# SCH.net
KiCad netlist of a schematic drawn in Altium Designer
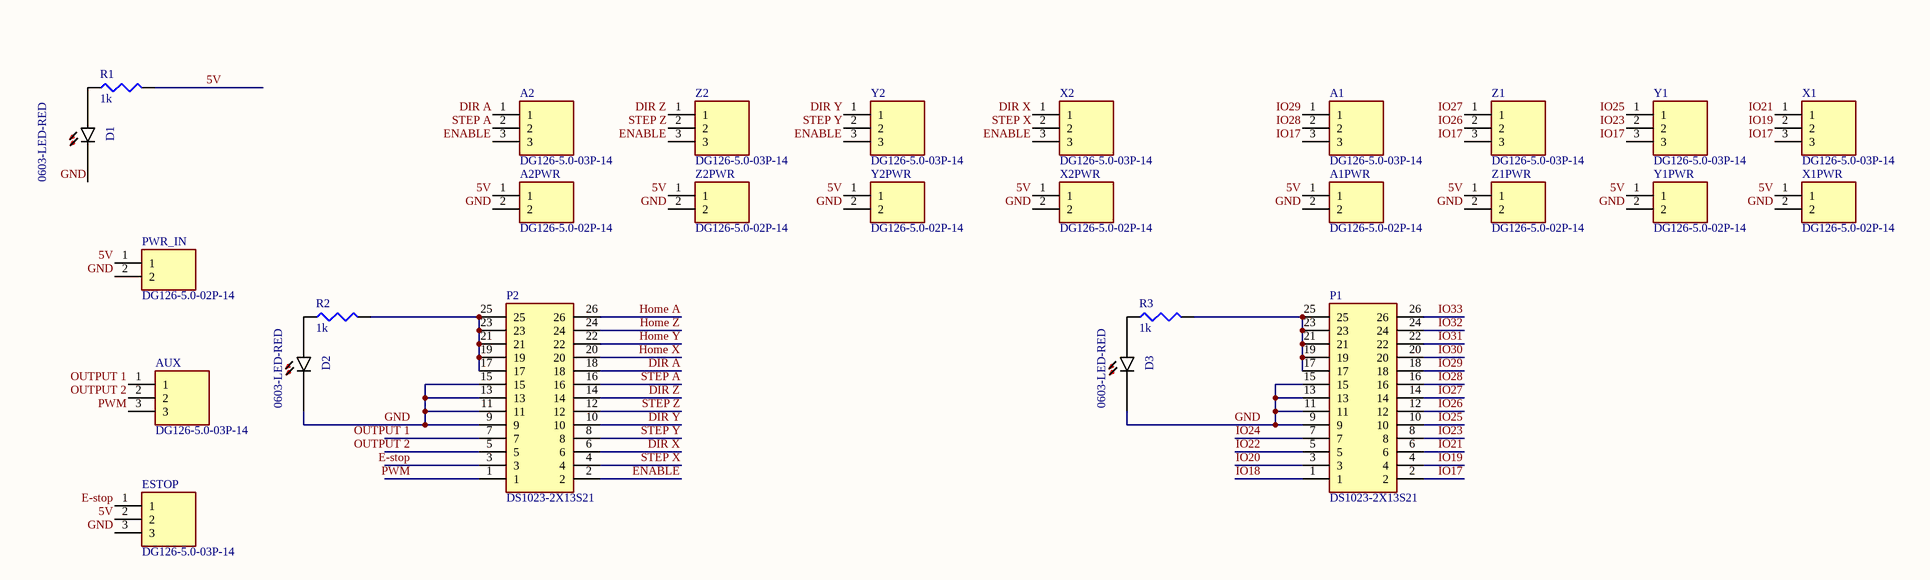
[diagram p0: SCH.SchDoc]

(export (version "E")
  (design (tool "Eeschema 10.0.6"))
  (components
    (comp (ref "A1")
      (value "DG126-5.0-03P-14")
      (footprint "SamacSys:DG1265003P1400AH")
      (description "Connector")
      (libsource (lib "*") (part "DG126-5.0-03P-14-00AH"))
    )
    (comp (ref "A1PWR")
      (value "DG126-5.0-02P-14")
      (footprint "SamacSys:DG1265002P1400AH")
      (description "Connector")
      (libsource (lib "*") (part "DG126-5.0-02P-14-00AH"))
    )
    (comp (ref "A2")
      (value "DG126-5.0-03P-14")
      (footprint "SamacSys:DG1265003P1400AH")
      (description "Connector")
      (libsource (lib "*") (part "DG126-5.0-03P-14-00AH"))
    )
    (comp (ref "A2PWR")
      (value "DG126-5.0-02P-14")
      (footprint "SamacSys:DG1265002P1400AH")
      (description "Connector")
      (libsource (lib "*") (part "DG126-5.0-02P-14-00AH"))
    )
    (comp (ref "AUX")
      (value "DG126-5.0-03P-14")
      (footprint "SamacSys:DG1265003P1400AH")
      (description "Connector")
      (libsource (lib "*") (part "DG126-5.0-03P-14-00AH"))
    )
    (comp (ref "D1")
      (value "0603-LED-RED")
      (footprint "*LEDM1608X80_LTE-C1906R-14(Primary)")
      (description "Red 620nm LED Indication - Discrete 2.2V 0603 (1608 Metric)")
      (fields (field (name "MP") "LTST-C194KRKT or SML-D12U1WT86"))
      (libsource (lib "lib") (part "0603-LED-RED"))
    )
    (comp (ref "D2")
      (value "0603-LED-RED")
      (footprint "*LEDM1608X80_LTE-C1906R-14(Primary)")
      (description "Red 620nm LED Indication - Discrete 2.2V 0603 (1608 Metric)")
      (fields (field (name "MP") "LTST-C194KRKT or SML-D12U1WT86"))
      (libsource (lib "lib") (part "0603-LED-RED"))
    )
    (comp (ref "D3")
      (value "0603-LED-RED")
      (footprint "*LEDM1608X80_LTE-C1906R-14(Primary)")
      (description "Red 620nm LED Indication - Discrete 2.2V 0603 (1608 Metric)")
      (fields (field (name "MP") "LTST-C194KRKT or SML-D12U1WT86"))
      (libsource (lib "lib") (part "0603-LED-RED"))
    )
    (comp (ref "ESTOP")
      (value "DG126-5.0-03P-14")
      (footprint "SamacSys:DG1265003P1400AH")
      (description "Connector")
      (libsource (lib "*") (part "DG126-5.0-03P-14-00AH"))
    )
    (comp (ref "P1")
      (value "DS1023-2X13S21")
      (footprint "SamacSys:DS10232X13S21")
      (description "Connector")
      (libsource (lib "*") (part "DS1023-2X13S21"))
    )
    (comp (ref "P2")
      (value "DS1023-2X13S21")
      (footprint "SamacSys:DS10232X13S21")
      (description "Connector")
      (libsource (lib "*") (part "DS1023-2X13S21"))
    )
    (comp (ref "PWR_IN")
      (value "DG126-5.0-02P-14")
      (footprint "SamacSys:DG1265002P1400AH")
      (description "Connector")
      (libsource (lib "*") (part "DG126-5.0-02P-14-00AH"))
    )
    (comp (ref "R1")
      (value "1k")
      (footprint "J1-0603")
      (description "1 kOhms ±1% 0.1W, 1/10W Chip Resistor 0603 (1608 Metric) Moisture Resistant Thick Film")
      (fields (field (name "MF") "Yageo or NXP") (field (name "MP") "RC0603FR-071KL"))
      (libsource (lib "lib") (part "RC0603FR-071KL"))
    )
    (comp (ref "R2")
      (value "1k")
      (footprint "J1-0603")
      (description "1 kOhms ±1% 0.1W, 1/10W Chip Resistor 0603 (1608 Metric) Moisture Resistant Thick Film")
      (fields (field (name "MF") "Yageo or NXP") (field (name "MP") "RC0603FR-071KL"))
      (libsource (lib "lib") (part "RC0603FR-071KL"))
    )
    (comp (ref "R3")
      (value "1k")
      (footprint "J1-0603")
      (description "1 kOhms ±1% 0.1W, 1/10W Chip Resistor 0603 (1608 Metric) Moisture Resistant Thick Film")
      (fields (field (name "MF") "Yageo or NXP") (field (name "MP") "RC0603FR-071KL"))
      (libsource (lib "lib") (part "RC0603FR-071KL"))
    )
    (comp (ref "X1")
      (value "DG126-5.0-03P-14")
      (footprint "SamacSys:DG1265003P1400AH")
      (description "Connector")
      (libsource (lib "*") (part "DG126-5.0-03P-14-00AH"))
    )
    (comp (ref "X1PWR")
      (value "DG126-5.0-02P-14")
      (footprint "SamacSys:DG1265002P1400AH")
      (description "Connector")
      (libsource (lib "*") (part "DG126-5.0-02P-14-00AH"))
    )
    (comp (ref "X2")
      (value "DG126-5.0-03P-14")
      (footprint "SamacSys:DG1265003P1400AH")
      (description "Connector")
      (libsource (lib "*") (part "DG126-5.0-03P-14-00AH"))
    )
    (comp (ref "X2PWR")
      (value "DG126-5.0-02P-14")
      (footprint "SamacSys:DG1265002P1400AH")
      (description "Connector")
      (libsource (lib "*") (part "DG126-5.0-02P-14-00AH"))
    )
    (comp (ref "Y1")
      (value "DG126-5.0-03P-14")
      (footprint "SamacSys:DG1265003P1400AH")
      (description "Connector")
      (libsource (lib "*") (part "DG126-5.0-03P-14-00AH"))
    )
    (comp (ref "Y1PWR")
      (value "DG126-5.0-02P-14")
      (footprint "SamacSys:DG1265002P1400AH")
      (description "Connector")
      (libsource (lib "*") (part "DG126-5.0-02P-14-00AH"))
    )
    (comp (ref "Y2")
      (value "DG126-5.0-03P-14")
      (footprint "SamacSys:DG1265003P1400AH")
      (description "Connector")
      (libsource (lib "*") (part "DG126-5.0-03P-14-00AH"))
    )
    (comp (ref "Y2PWR")
      (value "DG126-5.0-02P-14")
      (footprint "SamacSys:DG1265002P1400AH")
      (description "Connector")
      (libsource (lib "*") (part "DG126-5.0-02P-14-00AH"))
    )
    (comp (ref "Z1")
      (value "DG126-5.0-03P-14")
      (footprint "SamacSys:DG1265003P1400AH")
      (description "Connector")
      (libsource (lib "*") (part "DG126-5.0-03P-14-00AH"))
    )
    (comp (ref "Z1PWR")
      (value "DG126-5.0-02P-14")
      (footprint "SamacSys:DG1265002P1400AH")
      (description "Connector")
      (libsource (lib "*") (part "DG126-5.0-02P-14-00AH"))
    )
    (comp (ref "Z2")
      (value "DG126-5.0-03P-14")
      (footprint "SamacSys:DG1265003P1400AH")
      (description "Connector")
      (libsource (lib "*") (part "DG126-5.0-03P-14-00AH"))
    )
    (comp (ref "Z2PWR")
      (value "DG126-5.0-02P-14")
      (footprint "SamacSys:DG1265002P1400AH")
      (description "Connector")
      (libsource (lib "*") (part "DG126-5.0-02P-14-00AH"))
    )
  )
  (nets
    (net (code "1") (name "/5V") (class "Default")
      (node (ref "A1PWR") (pin "1") (pinfunction "1_1") (pintype "passive"))
      (node (ref "A2PWR") (pin "1") (pinfunction "1_1") (pintype "passive"))
      (node (ref "ESTOP") (pin "2") (pinfunction "2_2") (pintype "passive"))
      (node (ref "PWR_IN") (pin "1") (pinfunction "1_1") (pintype "passive"))
      (node (ref "R1") (pin "2") (pinfunction "2_2") (pintype "passive"))
      (node (ref "X1PWR") (pin "1") (pinfunction "1_1") (pintype "passive"))
      (node (ref "X2PWR") (pin "1") (pinfunction "1_1") (pintype "passive"))
      (node (ref "Y1PWR") (pin "1") (pinfunction "1_1") (pintype "passive"))
      (node (ref "Y2PWR") (pin "1") (pinfunction "1_1") (pintype "passive"))
      (node (ref "Z1PWR") (pin "1") (pinfunction "1_1") (pintype "passive"))
      (node (ref "Z2PWR") (pin "1") (pinfunction "1_1") (pintype "passive"))
    )
    (net (code "2") (name "/DIR A") (class "Default")
      (node (ref "A2") (pin "1") (pinfunction "1_1") (pintype "passive"))
      (node (ref "P2") (pin "18") (pinfunction "18_18") (pintype "passive"))
    )
    (net (code "3") (name "/DIR X") (class "Default")
      (node (ref "P2") (pin "6") (pinfunction "6_6") (pintype "passive"))
      (node (ref "X2") (pin "1") (pinfunction "1_1") (pintype "passive"))
    )
    (net (code "4") (name "/DIR Y") (class "Default")
      (node (ref "P2") (pin "10") (pinfunction "10_10") (pintype "passive"))
      (node (ref "Y2") (pin "1") (pinfunction "1_1") (pintype "passive"))
    )
    (net (code "5") (name "/DIR Z") (class "Default")
      (node (ref "P2") (pin "14") (pinfunction "14_14") (pintype "passive"))
      (node (ref "Z2") (pin "1") (pinfunction "1_1") (pintype "passive"))
    )
    (net (code "6") (name "/E-stop") (class "Default")
      (node (ref "ESTOP") (pin "1") (pinfunction "1_1") (pintype "passive"))
      (node (ref "P2") (pin "3") (pinfunction "3_3") (pintype "passive"))
    )
    (net (code "7") (name "/ENABLE") (class "Default")
      (node (ref "A2") (pin "3") (pinfunction "3_3") (pintype "passive"))
      (node (ref "P2") (pin "2") (pinfunction "2_2") (pintype "passive"))
      (node (ref "X2") (pin "3") (pinfunction "3_3") (pintype "passive"))
      (node (ref "Y2") (pin "3") (pinfunction "3_3") (pintype "passive"))
      (node (ref "Z2") (pin "3") (pinfunction "3_3") (pintype "passive"))
    )
    (net (code "8") (name "/GND") (class "Default")
      (node (ref "A1PWR") (pin "2") (pinfunction "2_2") (pintype "passive"))
      (node (ref "A2PWR") (pin "2") (pinfunction "2_2") (pintype "passive"))
      (node (ref "D1") (pin "C") (pinfunction "C_C") (pintype "passive"))
      (node (ref "D2") (pin "C") (pinfunction "C_C") (pintype "passive"))
      (node (ref "D3") (pin "C") (pinfunction "C_C") (pintype "passive"))
      (node (ref "ESTOP") (pin "3") (pinfunction "3_3") (pintype "passive"))
      (node (ref "P1") (pin "11") (pinfunction "11_11") (pintype "passive"))
      (node (ref "P1") (pin "13") (pinfunction "13_13") (pintype "passive"))
      (node (ref "P1") (pin "15") (pinfunction "15_15") (pintype "passive"))
      (node (ref "P1") (pin "9") (pinfunction "9_9") (pintype "passive"))
      (node (ref "P2") (pin "11") (pinfunction "11_11") (pintype "passive"))
      (node (ref "P2") (pin "13") (pinfunction "13_13") (pintype "passive"))
      (node (ref "P2") (pin "15") (pinfunction "15_15") (pintype "passive"))
      (node (ref "P2") (pin "9") (pinfunction "9_9") (pintype "passive"))
      (node (ref "PWR_IN") (pin "2") (pinfunction "2_2") (pintype "passive"))
      (node (ref "X1PWR") (pin "2") (pinfunction "2_2") (pintype "passive"))
      (node (ref "X2PWR") (pin "2") (pinfunction "2_2") (pintype "passive"))
      (node (ref "Y1PWR") (pin "2") (pinfunction "2_2") (pintype "passive"))
      (node (ref "Y2PWR") (pin "2") (pinfunction "2_2") (pintype "passive"))
      (node (ref "Z1PWR") (pin "2") (pinfunction "2_2") (pintype "passive"))
      (node (ref "Z2PWR") (pin "2") (pinfunction "2_2") (pintype "passive"))
    )
    (net (code "9") (name "/Home A") (class "Default")
      (node (ref "P2") (pin "26") (pinfunction "26_26") (pintype "passive"))
    )
    (net (code "10") (name "/Home X") (class "Default")
      (node (ref "P2") (pin "20") (pinfunction "20_20") (pintype "passive"))
    )
    (net (code "11") (name "/Home Y") (class "Default")
      (node (ref "P2") (pin "22") (pinfunction "22_22") (pintype "passive"))
    )
    (net (code "12") (name "/Home Z") (class "Default")
      (node (ref "P2") (pin "24") (pinfunction "24_24") (pintype "passive"))
    )
    (net (code "13") (name "/IO17") (class "Default")
      (node (ref "A1") (pin "3") (pinfunction "3_3") (pintype "passive"))
      (node (ref "P1") (pin "2") (pinfunction "2_2") (pintype "passive"))
      (node (ref "X1") (pin "3") (pinfunction "3_3") (pintype "passive"))
      (node (ref "Y1") (pin "3") (pinfunction "3_3") (pintype "passive"))
      (node (ref "Z1") (pin "3") (pinfunction "3_3") (pintype "passive"))
    )
    (net (code "14") (name "/IO18") (class "Default")
      (node (ref "P1") (pin "1") (pinfunction "1_1") (pintype "passive"))
    )
    (net (code "15") (name "/IO19") (class "Default")
      (node (ref "P1") (pin "4") (pinfunction "4_4") (pintype "passive"))
      (node (ref "X1") (pin "2") (pinfunction "2_2") (pintype "passive"))
    )
    (net (code "16") (name "/IO20") (class "Default")
      (node (ref "P1") (pin "3") (pinfunction "3_3") (pintype "passive"))
    )
    (net (code "17") (name "/IO21") (class "Default")
      (node (ref "P1") (pin "6") (pinfunction "6_6") (pintype "passive"))
      (node (ref "X1") (pin "1") (pinfunction "1_1") (pintype "passive"))
    )
    (net (code "18") (name "/IO22") (class "Default")
      (node (ref "P1") (pin "5") (pinfunction "5_5") (pintype "passive"))
    )
    (net (code "19") (name "/IO23") (class "Default")
      (node (ref "P1") (pin "8") (pinfunction "8_8") (pintype "passive"))
      (node (ref "Y1") (pin "2") (pinfunction "2_2") (pintype "passive"))
    )
    (net (code "20") (name "/IO24") (class "Default")
      (node (ref "P1") (pin "7") (pinfunction "7_7") (pintype "passive"))
    )
    (net (code "21") (name "/IO25") (class "Default")
      (node (ref "P1") (pin "10") (pinfunction "10_10") (pintype "passive"))
      (node (ref "Y1") (pin "1") (pinfunction "1_1") (pintype "passive"))
    )
    (net (code "22") (name "/IO26") (class "Default")
      (node (ref "P1") (pin "12") (pinfunction "12_12") (pintype "passive"))
      (node (ref "Z1") (pin "2") (pinfunction "2_2") (pintype "passive"))
    )
    (net (code "23") (name "/IO27") (class "Default")
      (node (ref "P1") (pin "14") (pinfunction "14_14") (pintype "passive"))
      (node (ref "Z1") (pin "1") (pinfunction "1_1") (pintype "passive"))
    )
    (net (code "24") (name "/IO28") (class "Default")
      (node (ref "A1") (pin "2") (pinfunction "2_2") (pintype "passive"))
      (node (ref "P1") (pin "16") (pinfunction "16_16") (pintype "passive"))
    )
    (net (code "25") (name "/IO29") (class "Default")
      (node (ref "A1") (pin "1") (pinfunction "1_1") (pintype "passive"))
      (node (ref "P1") (pin "18") (pinfunction "18_18") (pintype "passive"))
    )
    (net (code "26") (name "/IO30") (class "Default")
      (node (ref "P1") (pin "20") (pinfunction "20_20") (pintype "passive"))
    )
    (net (code "27") (name "/IO31") (class "Default")
      (node (ref "P1") (pin "22") (pinfunction "22_22") (pintype "passive"))
    )
    (net (code "28") (name "/IO32") (class "Default")
      (node (ref "P1") (pin "24") (pinfunction "24_24") (pintype "passive"))
    )
    (net (code "29") (name "/IO33") (class "Default")
      (node (ref "P1") (pin "26") (pinfunction "26_26") (pintype "passive"))
    )
    (net (code "30") (name "/OUTPUT 1") (class "Default")
      (node (ref "AUX") (pin "1") (pinfunction "1_1") (pintype "passive"))
      (node (ref "P2") (pin "7") (pinfunction "7_7") (pintype "passive"))
    )
    (net (code "31") (name "/OUTPUT 2") (class "Default")
      (node (ref "AUX") (pin "2") (pinfunction "2_2") (pintype "passive"))
      (node (ref "P2") (pin "5") (pinfunction "5_5") (pintype "passive"))
    )
    (net (code "32") (name "/PWM") (class "Default")
      (node (ref "AUX") (pin "3") (pinfunction "3_3") (pintype "passive"))
      (node (ref "P2") (pin "1") (pinfunction "1_1") (pintype "passive"))
    )
    (net (code "33") (name "/STEP A") (class "Default")
      (node (ref "A2") (pin "2") (pinfunction "2_2") (pintype "passive"))
      (node (ref "P2") (pin "16") (pinfunction "16_16") (pintype "passive"))
    )
    (net (code "34") (name "/STEP X") (class "Default")
      (node (ref "P2") (pin "4") (pinfunction "4_4") (pintype "passive"))
      (node (ref "X2") (pin "2") (pinfunction "2_2") (pintype "passive"))
    )
    (net (code "35") (name "/STEP Y") (class "Default")
      (node (ref "P2") (pin "8") (pinfunction "8_8") (pintype "passive"))
      (node (ref "Y2") (pin "2") (pinfunction "2_2") (pintype "passive"))
    )
    (net (code "36") (name "/STEP Z") (class "Default")
      (node (ref "P2") (pin "12") (pinfunction "12_12") (pintype "passive"))
      (node (ref "Z2") (pin "2") (pinfunction "2_2") (pintype "passive"))
    )
    (net (code "37") (name "Net-(D1-PadA)") (class "Default")
      (node (ref "D1") (pin "A") (pinfunction "A_A") (pintype "passive"))
      (node (ref "R1") (pin "1") (pinfunction "1_1") (pintype "passive"))
    )
    (net (code "38") (name "Net-(D2-PadA)") (class "Default")
      (node (ref "D2") (pin "A") (pinfunction "A_A") (pintype "passive"))
      (node (ref "R2") (pin "1") (pinfunction "1_1") (pintype "passive"))
    )
    (net (code "39") (name "Net-(D3-PadA)") (class "Default")
      (node (ref "D3") (pin "A") (pinfunction "A_A") (pintype "passive"))
      (node (ref "R3") (pin "1") (pinfunction "1_1") (pintype "passive"))
    )
    (net (code "40") (name "Net-(P1-Pad17)") (class "Default")
      (node (ref "P1") (pin "17") (pinfunction "17_17") (pintype "passive"))
      (node (ref "P1") (pin "19") (pinfunction "19_19") (pintype "passive"))
      (node (ref "P1") (pin "21") (pinfunction "21_21") (pintype "passive"))
      (node (ref "P1") (pin "23") (pinfunction "23_23") (pintype "passive"))
      (node (ref "P1") (pin "25") (pinfunction "25_25") (pintype "passive"))
      (node (ref "R3") (pin "2") (pinfunction "2_2") (pintype "passive"))
    )
    (net (code "41") (name "Net-(P2-Pad17)") (class "Default")
      (node (ref "P2") (pin "17") (pinfunction "17_17") (pintype "passive"))
      (node (ref "P2") (pin "19") (pinfunction "19_19") (pintype "passive"))
      (node (ref "P2") (pin "21") (pinfunction "21_21") (pintype "passive"))
      (node (ref "P2") (pin "23") (pinfunction "23_23") (pintype "passive"))
      (node (ref "P2") (pin "25") (pinfunction "25_25") (pintype "passive"))
      (node (ref "R2") (pin "2") (pinfunction "2_2") (pintype "passive"))
    )
  )
)
